# Matrix.net
KiCad netlist of a schematic drawn in Altium Designer
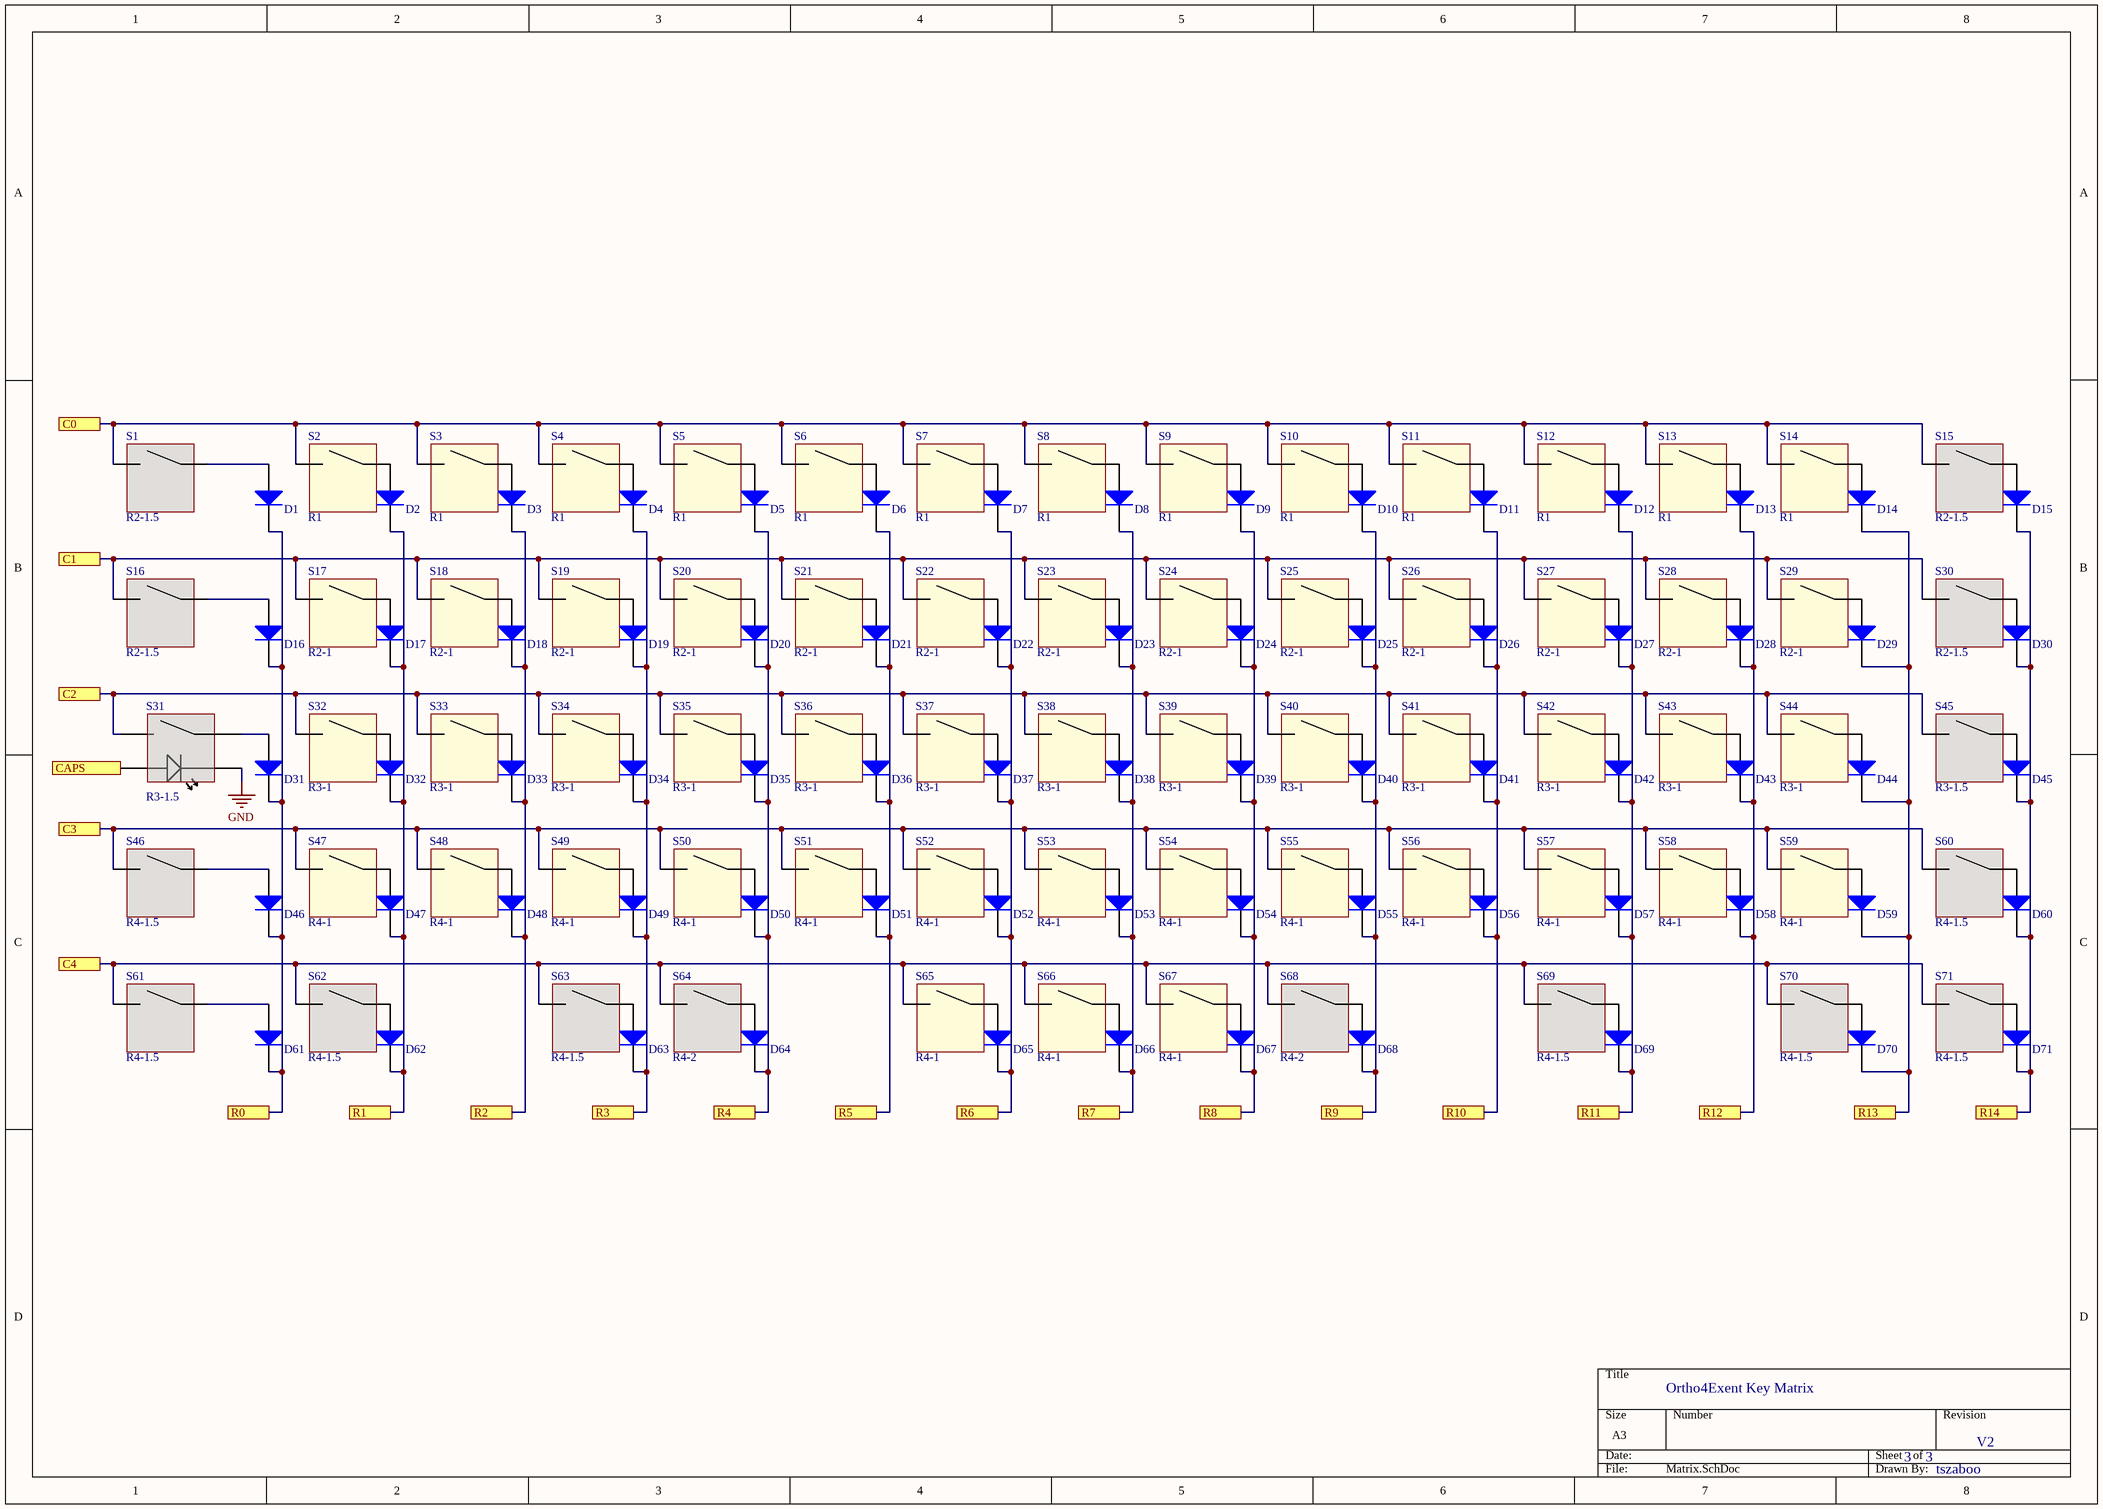
[diagram p0: Matrix.SchDoc]

(export (version "E")
  (design (tool "Eeschema 10.0.6"))
  (components
    (comp (ref "D1")
      (value "1N4148WS")
      (footprint "SOD323FL")
      (description "Default Diode")
      (libsource (lib "Rectifier") (part "Diode"))
    )
    (comp (ref "D2")
      (value "1N4148WS")
      (footprint "SOD323FL")
      (description "Default Diode")
      (libsource (lib "Rectifier") (part "Diode"))
    )
    (comp (ref "D3")
      (value "1N4148WS")
      (footprint "SOD323FL")
      (description "Default Diode")
      (libsource (lib "Rectifier") (part "Diode"))
    )
    (comp (ref "D4")
      (value "1N4148WS")
      (footprint "SOD323FL")
      (description "Default Diode")
      (libsource (lib "Rectifier") (part "Diode"))
    )
    (comp (ref "D5")
      (value "1N4148WS")
      (footprint "SOD323FL")
      (description "Default Diode")
      (libsource (lib "Rectifier") (part "Diode"))
    )
    (comp (ref "D6")
      (value "1N4148WS")
      (footprint "SOD323FL")
      (description "Default Diode")
      (libsource (lib "Rectifier") (part "Diode"))
    )
    (comp (ref "D7")
      (value "1N4148WS")
      (footprint "SOD323FL")
      (description "Default Diode")
      (libsource (lib "Rectifier") (part "Diode"))
    )
    (comp (ref "D8")
      (value "1N4148WS")
      (footprint "SOD323FL")
      (description "Default Diode")
      (libsource (lib "Rectifier") (part "Diode"))
    )
    (comp (ref "D9")
      (value "1N4148WS")
      (footprint "SOD323FL")
      (description "Default Diode")
      (libsource (lib "Rectifier") (part "Diode"))
    )
    (comp (ref "D10")
      (value "1N4148WS")
      (footprint "SOD323FL")
      (description "Default Diode")
      (libsource (lib "Rectifier") (part "Diode"))
    )
    (comp (ref "D11")
      (value "1N4148WS")
      (footprint "SOD323FL")
      (description "Default Diode")
      (libsource (lib "Rectifier") (part "Diode"))
    )
    (comp (ref "D12")
      (value "1N4148WS")
      (footprint "SOD323FL")
      (description "Default Diode")
      (libsource (lib "Rectifier") (part "Diode"))
    )
    (comp (ref "D13")
      (value "1N4148WS")
      (footprint "SOD323FL")
      (description "Default Diode")
      (libsource (lib "Rectifier") (part "Diode"))
    )
    (comp (ref "D14")
      (value "1N4148WS")
      (footprint "SOD323FL")
      (description "Default Diode")
      (libsource (lib "Rectifier") (part "Diode"))
    )
    (comp (ref "D15")
      (value "1N4148WS")
      (footprint "SOD323FL")
      (description "Default Diode")
      (libsource (lib "Rectifier") (part "Diode"))
    )
    (comp (ref "D16")
      (value "1N4148WS")
      (footprint "SOD323FL")
      (description "Default Diode")
      (libsource (lib "Rectifier") (part "Diode"))
    )
    (comp (ref "D17")
      (value "1N4148WS")
      (footprint "SOD323FL")
      (description "Default Diode")
      (libsource (lib "Rectifier") (part "Diode"))
    )
    (comp (ref "D18")
      (value "1N4148WS")
      (footprint "SOD323FL")
      (description "Default Diode")
      (libsource (lib "Rectifier") (part "Diode"))
    )
    (comp (ref "D19")
      (value "1N4148WS")
      (footprint "SOD323FL")
      (description "Default Diode")
      (libsource (lib "Rectifier") (part "Diode"))
    )
    (comp (ref "D20")
      (value "1N4148WS")
      (footprint "SOD323FL")
      (description "Default Diode")
      (libsource (lib "Rectifier") (part "Diode"))
    )
    (comp (ref "D21")
      (value "1N4148WS")
      (footprint "SOD323FL")
      (description "Default Diode")
      (libsource (lib "Rectifier") (part "Diode"))
    )
    (comp (ref "D22")
      (value "1N4148WS")
      (footprint "SOD323FL")
      (description "Default Diode")
      (libsource (lib "Rectifier") (part "Diode"))
    )
    (comp (ref "D23")
      (value "1N4148WS")
      (footprint "SOD323FL")
      (description "Default Diode")
      (libsource (lib "Rectifier") (part "Diode"))
    )
    (comp (ref "D24")
      (value "1N4148WS")
      (footprint "SOD323FL")
      (description "Default Diode")
      (libsource (lib "Rectifier") (part "Diode"))
    )
    (comp (ref "D25")
      (value "1N4148WS")
      (footprint "SOD323FL")
      (description "Default Diode")
      (libsource (lib "Rectifier") (part "Diode"))
    )
    (comp (ref "D26")
      (value "1N4148WS")
      (footprint "SOD323FL")
      (description "Default Diode")
      (libsource (lib "Rectifier") (part "Diode"))
    )
    (comp (ref "D27")
      (value "1N4148WS")
      (footprint "SOD323FL")
      (description "Default Diode")
      (libsource (lib "Rectifier") (part "Diode"))
    )
    (comp (ref "D28")
      (value "1N4148WS")
      (footprint "SOD323FL")
      (description "Default Diode")
      (libsource (lib "Rectifier") (part "Diode"))
    )
    (comp (ref "D29")
      (value "1N4148WS")
      (footprint "SOD323FL")
      (description "Default Diode")
      (libsource (lib "Rectifier") (part "Diode"))
    )
    (comp (ref "D30")
      (value "1N4148WS")
      (footprint "SOD323FL")
      (description "Default Diode")
      (libsource (lib "Rectifier") (part "Diode"))
    )
    (comp (ref "D31")
      (value "1N4148WS")
      (footprint "SOD323FL")
      (description "Default Diode")
      (libsource (lib "Rectifier") (part "Diode"))
    )
    (comp (ref "D32")
      (value "1N4148WS")
      (footprint "SOD323FL")
      (description "Default Diode")
      (libsource (lib "Rectifier") (part "Diode"))
    )
    (comp (ref "D33")
      (value "1N4148WS")
      (footprint "SOD323FL")
      (description "Default Diode")
      (libsource (lib "Rectifier") (part "Diode"))
    )
    (comp (ref "D34")
      (value "1N4148WS")
      (footprint "SOD323FL")
      (description "Default Diode")
      (libsource (lib "Rectifier") (part "Diode"))
    )
    (comp (ref "D35")
      (value "1N4148WS")
      (footprint "SOD323FL")
      (description "Default Diode")
      (libsource (lib "Rectifier") (part "Diode"))
    )
    (comp (ref "D36")
      (value "1N4148WS")
      (footprint "SOD323FL")
      (description "Default Diode")
      (libsource (lib "Rectifier") (part "Diode"))
    )
    (comp (ref "D37")
      (value "1N4148WS")
      (footprint "SOD323FL")
      (description "Default Diode")
      (libsource (lib "Rectifier") (part "Diode"))
    )
    (comp (ref "D38")
      (value "1N4148WS")
      (footprint "SOD323FL")
      (description "Default Diode")
      (libsource (lib "Rectifier") (part "Diode"))
    )
    (comp (ref "D39")
      (value "1N4148WS")
      (footprint "SOD323FL")
      (description "Default Diode")
      (libsource (lib "Rectifier") (part "Diode"))
    )
    (comp (ref "D40")
      (value "1N4148WS")
      (footprint "SOD323FL")
      (description "Default Diode")
      (libsource (lib "Rectifier") (part "Diode"))
    )
    (comp (ref "D41")
      (value "1N4148WS")
      (footprint "SOD323FL")
      (description "Default Diode")
      (libsource (lib "Rectifier") (part "Diode"))
    )
    (comp (ref "D42")
      (value "1N4148WS")
      (footprint "SOD323FL")
      (description "Default Diode")
      (libsource (lib "Rectifier") (part "Diode"))
    )
    (comp (ref "D43")
      (value "1N4148WS")
      (footprint "SOD323FL")
      (description "Default Diode")
      (libsource (lib "Rectifier") (part "Diode"))
    )
    (comp (ref "D44")
      (value "1N4148WS")
      (footprint "SOD323FL")
      (description "Default Diode")
      (libsource (lib "Rectifier") (part "Diode"))
    )
    (comp (ref "D45")
      (value "1N4148WS")
      (footprint "SOD323FL")
      (description "Default Diode")
      (libsource (lib "Rectifier") (part "Diode"))
    )
    (comp (ref "D46")
      (value "1N4148WS")
      (footprint "SOD323FL")
      (description "Default Diode")
      (libsource (lib "Rectifier") (part "Diode"))
    )
    (comp (ref "D47")
      (value "1N4148WS")
      (footprint "SOD323FL")
      (description "Default Diode")
      (libsource (lib "Rectifier") (part "Diode"))
    )
    (comp (ref "D48")
      (value "1N4148WS")
      (footprint "SOD323FL")
      (description "Default Diode")
      (libsource (lib "Rectifier") (part "Diode"))
    )
    (comp (ref "D49")
      (value "1N4148WS")
      (footprint "SOD323FL")
      (description "Default Diode")
      (libsource (lib "Rectifier") (part "Diode"))
    )
    (comp (ref "D50")
      (value "1N4148WS")
      (footprint "SOD323FL")
      (description "Default Diode")
      (libsource (lib "Rectifier") (part "Diode"))
    )
    (comp (ref "D51")
      (value "1N4148WS")
      (footprint "SOD323FL")
      (description "Default Diode")
      (libsource (lib "Rectifier") (part "Diode"))
    )
    (comp (ref "D52")
      (value "1N4148WS")
      (footprint "SOD323FL")
      (description "Default Diode")
      (libsource (lib "Rectifier") (part "Diode"))
    )
    (comp (ref "D53")
      (value "1N4148WS")
      (footprint "SOD323FL")
      (description "Default Diode")
      (libsource (lib "Rectifier") (part "Diode"))
    )
    (comp (ref "D54")
      (value "1N4148WS")
      (footprint "SOD323FL")
      (description "Default Diode")
      (libsource (lib "Rectifier") (part "Diode"))
    )
    (comp (ref "D55")
      (value "1N4148WS")
      (footprint "SOD323FL")
      (description "Default Diode")
      (libsource (lib "Rectifier") (part "Diode"))
    )
    (comp (ref "D56")
      (value "1N4148WS")
      (footprint "SOD323FL")
      (description "Default Diode")
      (libsource (lib "Rectifier") (part "Diode"))
    )
    (comp (ref "D57")
      (value "1N4148WS")
      (footprint "SOD323FL")
      (description "Default Diode")
      (libsource (lib "Rectifier") (part "Diode"))
    )
    (comp (ref "D58")
      (value "1N4148WS")
      (footprint "SOD323FL")
      (description "Default Diode")
      (libsource (lib "Rectifier") (part "Diode"))
    )
    (comp (ref "D59")
      (value "1N4148WS")
      (footprint "SOD323FL")
      (description "Default Diode")
      (libsource (lib "Rectifier") (part "Diode"))
    )
    (comp (ref "D60")
      (value "1N4148WS")
      (footprint "SOD323FL")
      (description "Default Diode")
      (libsource (lib "Rectifier") (part "Diode"))
    )
    (comp (ref "D61")
      (value "1N4148WS")
      (footprint "SOD323FL")
      (description "Default Diode")
      (libsource (lib "Rectifier") (part "Diode"))
    )
    (comp (ref "D62")
      (value "1N4148WS")
      (footprint "SOD323FL")
      (description "Default Diode")
      (libsource (lib "Rectifier") (part "Diode"))
    )
    (comp (ref "D63")
      (value "1N4148WS")
      (footprint "SOD323FL")
      (description "Default Diode")
      (libsource (lib "Rectifier") (part "Diode"))
    )
    (comp (ref "D64")
      (value "1N4148WS")
      (footprint "SOD323FL")
      (description "Default Diode")
      (libsource (lib "Rectifier") (part "Diode"))
    )
    (comp (ref "D65")
      (value "1N4148WS")
      (footprint "SOD323FL")
      (description "Default Diode")
      (libsource (lib "Rectifier") (part "Diode"))
    )
    (comp (ref "D66")
      (value "1N4148WS")
      (footprint "SOD323FL")
      (description "Default Diode")
      (libsource (lib "Rectifier") (part "Diode"))
    )
    (comp (ref "D67")
      (value "1N4148WS")
      (footprint "SOD323FL")
      (description "Default Diode")
      (libsource (lib "Rectifier") (part "Diode"))
    )
    (comp (ref "D68")
      (value "1N4148WS")
      (footprint "SOD323FL")
      (description "Default Diode")
      (libsource (lib "Rectifier") (part "Diode"))
    )
    (comp (ref "D69")
      (value "1N4148WS")
      (footprint "SOD323FL")
      (description "Default Diode")
      (libsource (lib "Rectifier") (part "Diode"))
    )
    (comp (ref "D70")
      (value "1N4148WS")
      (footprint "SOD323FL")
      (description "Default Diode")
      (libsource (lib "Rectifier") (part "Diode"))
    )
    (comp (ref "D71")
      (value "1N4148WS")
      (footprint "SOD323FL")
      (description "Default Diode")
      (libsource (lib "Rectifier") (part "Diode"))
    )
    (comp (ref "S1")
      (value "R2-1.5")
      (footprint "MX:R2-1.5 NOLED")
      (libsource (lib "MX-NOLED") (part "R2-1.5"))
    )
    (comp (ref "S2") (value "R1") (footprint "R1 NOLED") (libsource (lib "MX-NOLED") (part "R1")))
    (comp (ref "S3") (value "R1") (footprint "R1 NOLED") (libsource (lib "MX-NOLED") (part "R1")))
    (comp (ref "S4") (value "R1") (footprint "R1 NOLED") (libsource (lib "MX-NOLED") (part "R1")))
    (comp (ref "S5") (value "R1") (footprint "R1 NOLED") (libsource (lib "MX-NOLED") (part "R1")))
    (comp (ref "S6") (value "R1") (footprint "R1 NOLED") (libsource (lib "MX-NOLED") (part "R1")))
    (comp (ref "S7") (value "R1") (footprint "R1 NOLED") (libsource (lib "MX-NOLED") (part "R1")))
    (comp (ref "S8") (value "R1") (footprint "R1-1 NOLED 180") (libsource (lib "MX-NOLED") (part "R1")))
    (comp (ref "S9") (value "R1") (footprint "R1 NOLED") (libsource (lib "MX-NOLED") (part "R1")))
    (comp (ref "S10") (value "R1") (footprint "R1 NOLED") (libsource (lib "MX-NOLED") (part "R1")))
    (comp (ref "S11") (value "R1") (footprint "R1 NOLED") (libsource (lib "MX-NOLED") (part "R1")))
    (comp (ref "S12") (value "R1") (footprint "R1 NOLED") (libsource (lib "MX-NOLED") (part "R1")))
    (comp (ref "S13") (value "R1") (footprint "R1 NOLED") (libsource (lib "MX-NOLED") (part "R1")))
    (comp (ref "S14") (value "R1") (footprint "R1 NOLED") (libsource (lib "MX-NOLED") (part "R1")))
    (comp (ref "S15")
      (value "R2-1.5")
      (footprint "MX:R2-1.5 NOLED")
      (libsource (lib "MX-NOLED") (part "R2-1.5"))
    )
    (comp (ref "S16")
      (value "R2-1.5")
      (footprint "MX:R2-1.5 NOLED")
      (libsource (lib "MX-NOLED") (part "R2-1.5"))
    )
    (comp (ref "S17") (value "R2-1") (footprint "R2-1 NOLED") (libsource (lib "MX-NOLED") (part "R2-1")))
    (comp (ref "S18") (value "R2-1") (footprint "R2-1 NOLED") (libsource (lib "MX-NOLED") (part "R2-1")))
    (comp (ref "S19") (value "R2-1") (footprint "R2-1 NOLED") (libsource (lib "MX-NOLED") (part "R2-1")))
    (comp (ref "S20") (value "R2-1") (footprint "R2-1 NOLED") (libsource (lib "MX-NOLED") (part "R2-1")))
    (comp (ref "S21") (value "R2-1") (footprint "R2-1 NOLED") (libsource (lib "MX-NOLED") (part "R2-1")))
    (comp (ref "S22") (value "R2-1") (footprint "R2-1 NOLED") (libsource (lib "MX-NOLED") (part "R2-1")))
    (comp (ref "S23") (value "R2-1") (footprint "R2-1 NOLED") (libsource (lib "MX-NOLED") (part "R2-1")))
    (comp (ref "S24") (value "R2-1") (footprint "R2-1 NOLED") (libsource (lib "MX-NOLED") (part "R2-1")))
    (comp (ref "S25") (value "R2-1") (footprint "R2-1 NOLED") (libsource (lib "MX-NOLED") (part "R2-1")))
    (comp (ref "S26") (value "R2-1") (footprint "R2-1 NOLED") (libsource (lib "MX-NOLED") (part "R2-1")))
    (comp (ref "S27") (value "R2-1") (footprint "R2-1 NOLED") (libsource (lib "MX-NOLED") (part "R2-1")))
    (comp (ref "S28") (value "R2-1") (footprint "R2-1 NOLED") (libsource (lib "MX-NOLED") (part "R2-1")))
    (comp (ref "S29") (value "R2-1") (footprint "R2-1 NOLED") (libsource (lib "MX-NOLED") (part "R2-1")))
    (comp (ref "S30")
      (value "R2-1.5")
      (footprint "MX:R2-1.5 NOLED")
      (libsource (lib "MX-NOLED") (part "R2-1.5"))
    )
    (comp (ref "S31") (value "R3-1.5") (footprint "R3-1.5") (libsource (lib "MX") (part "R3-1.5")))
    (comp (ref "S32") (value "R3-1") (footprint "R3-1 NOLED") (libsource (lib "MX-NOLED") (part "R3-1")))
    (comp (ref "S33") (value "R3-1") (footprint "R3-1 NOLED") (libsource (lib "MX-NOLED") (part "R3-1")))
    (comp (ref "S34") (value "R3-1") (footprint "R3-1 NOLED") (libsource (lib "MX-NOLED") (part "R3-1")))
    (comp (ref "S35") (value "R3-1") (footprint "R3-1 NOLED") (libsource (lib "MX-NOLED") (part "R3-1")))
    (comp (ref "S36") (value "R3-1") (footprint "R3-1 NOLED") (libsource (lib "MX-NOLED") (part "R3-1")))
    (comp (ref "S37") (value "R3-1") (footprint "R3-1 NOLED") (libsource (lib "MX-NOLED") (part "R3-1")))
    (comp (ref "S38") (value "R3-1") (footprint "R3-1 NOLED") (libsource (lib "MX-NOLED") (part "R3-1")))
    (comp (ref "S39") (value "R3-1") (footprint "R3-1 NOLED") (libsource (lib "MX-NOLED") (part "R3-1")))
    (comp (ref "S40") (value "R3-1") (footprint "R3-1 NOLED") (libsource (lib "MX-NOLED") (part "R3-1")))
    (comp (ref "S41") (value "R3-1") (footprint "R3-1 NOLED") (libsource (lib "MX-NOLED") (part "R3-1")))
    (comp (ref "S42") (value "R3-1") (footprint "R3-1 NOLED") (libsource (lib "MX-NOLED") (part "R3-1")))
    (comp (ref "S43") (value "R3-1") (footprint "R3-1 NOLED") (libsource (lib "MX-NOLED") (part "R3-1")))
    (comp (ref "S44") (value "R3-1") (footprint "R3-1 NOLED") (libsource (lib "MX-NOLED") (part "R3-1")))
    (comp (ref "S45")
      (value "R3-1.5")
      (footprint "R3-1.5 NOLED")
      (libsource (lib "MX-NOLED") (part "R3-1.5"))
    )
    (comp (ref "S46")
      (value "R4-1.5")
      (footprint "R4-1.5 NOLED")
      (libsource (lib "MX-NOLED") (part "R4-1.5"))
    )
    (comp (ref "S47") (value "R4-1") (footprint "R4-1 NOLED") (libsource (lib "MX-NOLED") (part "R4-1")))
    (comp (ref "S48") (value "R4-1") (footprint "R4-1 NOLED") (libsource (lib "MX-NOLED") (part "R4-1")))
    (comp (ref "S49") (value "R4-1") (footprint "R4-1 NOLED") (libsource (lib "MX-NOLED") (part "R4-1")))
    (comp (ref "S50") (value "R4-1") (footprint "R4-1 NOLED") (libsource (lib "MX-NOLED") (part "R4-1")))
    (comp (ref "S51") (value "R4-1") (footprint "R4-1 NOLED") (libsource (lib "MX-NOLED") (part "R4-1")))
    (comp (ref "S52") (value "R4-1") (footprint "R4-1 NOLED") (libsource (lib "MX-NOLED") (part "R4-1")))
    (comp (ref "S53") (value "R4-1") (footprint "R4-1 NOLED") (libsource (lib "MX-NOLED") (part "R4-1")))
    (comp (ref "S54") (value "R4-1") (footprint "R4-1 NOLED") (libsource (lib "MX-NOLED") (part "R4-1")))
    (comp (ref "S55") (value "R4-1") (footprint "R4-1 NOLED") (libsource (lib "MX-NOLED") (part "R4-1")))
    (comp (ref "S56") (value "R4-1") (footprint "R4-1 NOLED") (libsource (lib "MX-NOLED") (part "R4-1")))
    (comp (ref "S57") (value "R4-1") (footprint "R4-1 NOLED") (libsource (lib "MX-NOLED") (part "R4-1")))
    (comp (ref "S58") (value "R4-1") (footprint "R4-1 NOLED") (libsource (lib "MX-NOLED") (part "R4-1")))
    (comp (ref "S59") (value "R4-1") (footprint "R4-1 NOLED") (libsource (lib "MX-NOLED") (part "R4-1")))
    (comp (ref "S60")
      (value "R4-1.5")
      (footprint "R4-1.5 NOLED")
      (libsource (lib "MX-NOLED") (part "R4-1.5"))
    )
    (comp (ref "S61")
      (value "R4-1.5")
      (footprint "R4-1.5 NOLED")
      (libsource (lib "MX-NOLED") (part "R4-1.5"))
    )
    (comp (ref "S62")
      (value "R4-1.5")
      (footprint "R4-1.5 NOLED")
      (libsource (lib "MX-NOLED") (part "R4-1.5"))
    )
    (comp (ref "S63")
      (value "R4-1.5")
      (footprint "R4-1.5 NOLED")
      (libsource (lib "MX-NOLED") (part "R4-1.5"))
    )
    (comp (ref "S64") (value "R4-2") (footprint "R4-2 NOLED 180") (libsource (lib "MX-NOLED") (part "R4-2")))
    (comp (ref "S65") (value "R4-1") (footprint "R4-1 NOLED") (libsource (lib "MX-NOLED") (part "R4-1")))
    (comp (ref "S66") (value "R4-1") (footprint "R4-1 NOLED") (libsource (lib "MX-NOLED") (part "R4-1")))
    (comp (ref "S67") (value "R4-1") (footprint "R4-1 NOLED") (libsource (lib "MX-NOLED") (part "R4-1")))
    (comp (ref "S68") (value "R4-2") (footprint "R4-2 NOLED 180") (libsource (lib "MX-NOLED") (part "R4-2")))
    (comp (ref "S69")
      (value "R4-1.5")
      (footprint "R4-1.5 NOLED")
      (libsource (lib "MX-NOLED") (part "R4-1.5"))
    )
    (comp (ref "S70")
      (value "R4-1.5")
      (footprint "R4-1.5 NOLED")
      (libsource (lib "MX-NOLED") (part "R4-1.5"))
    )
    (comp (ref "S71")
      (value "R4-1.5")
      (footprint "R4-1.5 NOLED")
      (libsource (lib "MX-NOLED") (part "R4-1.5"))
    )
  )
  (nets
    (net (code "1") (name "/C0") (class "Default")
      (node (ref "S1") (pin "1") (pinfunction "1_1") (pintype "passive"))
      (node (ref "S10") (pin "1") (pinfunction "1_1") (pintype "passive"))
      (node (ref "S11") (pin "1") (pinfunction "1_1") (pintype "passive"))
      (node (ref "S12") (pin "1") (pinfunction "1_1") (pintype "passive"))
      (node (ref "S13") (pin "1") (pinfunction "1_1") (pintype "passive"))
      (node (ref "S14") (pin "1") (pinfunction "1_1") (pintype "passive"))
      (node (ref "S15") (pin "1") (pinfunction "1_1") (pintype "passive"))
      (node (ref "S2") (pin "1") (pinfunction "1_1") (pintype "passive"))
      (node (ref "S3") (pin "1") (pinfunction "1_1") (pintype "passive"))
      (node (ref "S4") (pin "1") (pinfunction "1_1") (pintype "passive"))
      (node (ref "S5") (pin "1") (pinfunction "1_1") (pintype "passive"))
      (node (ref "S6") (pin "1") (pinfunction "1_1") (pintype "passive"))
      (node (ref "S7") (pin "1") (pinfunction "1_1") (pintype "passive"))
      (node (ref "S8") (pin "1") (pinfunction "1_1") (pintype "passive"))
      (node (ref "S9") (pin "1") (pinfunction "1_1") (pintype "passive"))
    )
    (net (code "2") (name "/C1") (class "Default")
      (node (ref "S16") (pin "1") (pinfunction "1_1") (pintype "passive"))
      (node (ref "S17") (pin "1") (pinfunction "1_1") (pintype "passive"))
      (node (ref "S18") (pin "1") (pinfunction "1_1") (pintype "passive"))
      (node (ref "S19") (pin "1") (pinfunction "1_1") (pintype "passive"))
      (node (ref "S20") (pin "1") (pinfunction "1_1") (pintype "passive"))
      (node (ref "S21") (pin "1") (pinfunction "1_1") (pintype "passive"))
      (node (ref "S22") (pin "1") (pinfunction "1_1") (pintype "passive"))
      (node (ref "S23") (pin "1") (pinfunction "1_1") (pintype "passive"))
      (node (ref "S24") (pin "1") (pinfunction "1_1") (pintype "passive"))
      (node (ref "S25") (pin "1") (pinfunction "1_1") (pintype "passive"))
      (node (ref "S26") (pin "1") (pinfunction "1_1") (pintype "passive"))
      (node (ref "S27") (pin "1") (pinfunction "1_1") (pintype "passive"))
      (node (ref "S28") (pin "1") (pinfunction "1_1") (pintype "passive"))
      (node (ref "S29") (pin "1") (pinfunction "1_1") (pintype "passive"))
      (node (ref "S30") (pin "1") (pinfunction "1_1") (pintype "passive"))
    )
    (net (code "3") (name "/C2") (class "Default")
      (node (ref "S31") (pin "1") (pinfunction "1_1") (pintype "passive"))
      (node (ref "S32") (pin "1") (pinfunction "1_1") (pintype "passive"))
      (node (ref "S33") (pin "1") (pinfunction "1_1") (pintype "passive"))
      (node (ref "S34") (pin "1") (pinfunction "1_1") (pintype "passive"))
      (node (ref "S35") (pin "1") (pinfunction "1_1") (pintype "passive"))
      (node (ref "S36") (pin "1") (pinfunction "1_1") (pintype "passive"))
      (node (ref "S37") (pin "1") (pinfunction "1_1") (pintype "passive"))
      (node (ref "S38") (pin "1") (pinfunction "1_1") (pintype "passive"))
      (node (ref "S39") (pin "1") (pinfunction "1_1") (pintype "passive"))
      (node (ref "S40") (pin "1") (pinfunction "1_1") (pintype "passive"))
      (node (ref "S41") (pin "1") (pinfunction "1_1") (pintype "passive"))
      (node (ref "S42") (pin "1") (pinfunction "1_1") (pintype "passive"))
      (node (ref "S43") (pin "1") (pinfunction "1_1") (pintype "passive"))
      (node (ref "S44") (pin "1") (pinfunction "1_1") (pintype "passive"))
      (node (ref "S45") (pin "1") (pinfunction "1_1") (pintype "passive"))
    )
    (net (code "4") (name "/C3") (class "Default")
      (node (ref "S46") (pin "1") (pinfunction "1_1") (pintype "passive"))
      (node (ref "S47") (pin "1") (pinfunction "1_1") (pintype "passive"))
      (node (ref "S48") (pin "1") (pinfunction "1_1") (pintype "passive"))
      (node (ref "S49") (pin "1") (pinfunction "1_1") (pintype "passive"))
      (node (ref "S50") (pin "1") (pinfunction "1_1") (pintype "passive"))
      (node (ref "S51") (pin "1") (pinfunction "1_1") (pintype "passive"))
      (node (ref "S52") (pin "1") (pinfunction "1_1") (pintype "passive"))
      (node (ref "S53") (pin "1") (pinfunction "1_1") (pintype "passive"))
      (node (ref "S54") (pin "1") (pinfunction "1_1") (pintype "passive"))
      (node (ref "S55") (pin "1") (pinfunction "1_1") (pintype "passive"))
      (node (ref "S56") (pin "1") (pinfunction "1_1") (pintype "passive"))
      (node (ref "S57") (pin "1") (pinfunction "1_1") (pintype "passive"))
      (node (ref "S58") (pin "1") (pinfunction "1_1") (pintype "passive"))
      (node (ref "S59") (pin "1") (pinfunction "1_1") (pintype "passive"))
      (node (ref "S60") (pin "1") (pinfunction "1_1") (pintype "passive"))
    )
    (net (code "5") (name "/C4") (class "Default")
      (node (ref "S61") (pin "1") (pinfunction "1_1") (pintype "passive"))
      (node (ref "S62") (pin "1") (pinfunction "1_1") (pintype "passive"))
      (node (ref "S63") (pin "1") (pinfunction "1_1") (pintype "passive"))
      (node (ref "S64") (pin "1") (pinfunction "1_1") (pintype "passive"))
      (node (ref "S65") (pin "1") (pinfunction "1_1") (pintype "passive"))
      (node (ref "S66") (pin "1") (pinfunction "1_1") (pintype "passive"))
      (node (ref "S67") (pin "1") (pinfunction "1_1") (pintype "passive"))
      (node (ref "S68") (pin "1") (pinfunction "1_1") (pintype "passive"))
      (node (ref "S69") (pin "1") (pinfunction "1_1") (pintype "passive"))
      (node (ref "S70") (pin "1") (pinfunction "1_1") (pintype "passive"))
      (node (ref "S71") (pin "1") (pinfunction "1_1") (pintype "passive"))
    )
    (net (code "6") (name "/CAPS") (class "Default")
      (node (ref "S31") (pin "4") (pinfunction "4_4") (pintype "passive"))
    )
    (net (code "7") (name "/R0") (class "Default")
      (node (ref "D1") (pin "2") (pinfunction "K_2") (pintype "passive"))
      (node (ref "D16") (pin "2") (pinfunction "K_2") (pintype "passive"))
      (node (ref "D31") (pin "2") (pinfunction "K_2") (pintype "passive"))
      (node (ref "D46") (pin "2") (pinfunction "K_2") (pintype "passive"))
      (node (ref "D61") (pin "2") (pinfunction "K_2") (pintype "passive"))
    )
    (net (code "8") (name "/R1") (class "Default")
      (node (ref "D17") (pin "2") (pinfunction "K_2") (pintype "passive"))
      (node (ref "D2") (pin "2") (pinfunction "K_2") (pintype "passive"))
      (node (ref "D32") (pin "2") (pinfunction "K_2") (pintype "passive"))
      (node (ref "D47") (pin "2") (pinfunction "K_2") (pintype "passive"))
      (node (ref "D62") (pin "2") (pinfunction "K_2") (pintype "passive"))
    )
    (net (code "9") (name "/R2") (class "Default")
      (node (ref "D18") (pin "2") (pinfunction "K_2") (pintype "passive"))
      (node (ref "D3") (pin "2") (pinfunction "K_2") (pintype "passive"))
      (node (ref "D33") (pin "2") (pinfunction "K_2") (pintype "passive"))
      (node (ref "D48") (pin "2") (pinfunction "K_2") (pintype "passive"))
    )
    (net (code "10") (name "/R3") (class "Default")
      (node (ref "D19") (pin "2") (pinfunction "K_2") (pintype "passive"))
      (node (ref "D34") (pin "2") (pinfunction "K_2") (pintype "passive"))
      (node (ref "D4") (pin "2") (pinfunction "K_2") (pintype "passive"))
      (node (ref "D49") (pin "2") (pinfunction "K_2") (pintype "passive"))
      (node (ref "D63") (pin "2") (pinfunction "K_2") (pintype "passive"))
    )
    (net (code "11") (name "/R4") (class "Default")
      (node (ref "D20") (pin "2") (pinfunction "K_2") (pintype "passive"))
      (node (ref "D35") (pin "2") (pinfunction "K_2") (pintype "passive"))
      (node (ref "D5") (pin "2") (pinfunction "K_2") (pintype "passive"))
      (node (ref "D50") (pin "2") (pinfunction "K_2") (pintype "passive"))
      (node (ref "D64") (pin "2") (pinfunction "K_2") (pintype "passive"))
    )
    (net (code "12") (name "/R5") (class "Default")
      (node (ref "D21") (pin "2") (pinfunction "K_2") (pintype "passive"))
      (node (ref "D36") (pin "2") (pinfunction "K_2") (pintype "passive"))
      (node (ref "D51") (pin "2") (pinfunction "K_2") (pintype "passive"))
      (node (ref "D6") (pin "2") (pinfunction "K_2") (pintype "passive"))
    )
    (net (code "13") (name "/R6") (class "Default")
      (node (ref "D22") (pin "2") (pinfunction "K_2") (pintype "passive"))
      (node (ref "D37") (pin "2") (pinfunction "K_2") (pintype "passive"))
      (node (ref "D52") (pin "2") (pinfunction "K_2") (pintype "passive"))
      (node (ref "D65") (pin "2") (pinfunction "K_2") (pintype "passive"))
      (node (ref "D7") (pin "2") (pinfunction "K_2") (pintype "passive"))
    )
    (net (code "14") (name "/R7") (class "Default")
      (node (ref "D23") (pin "2") (pinfunction "K_2") (pintype "passive"))
      (node (ref "D38") (pin "2") (pinfunction "K_2") (pintype "passive"))
      (node (ref "D53") (pin "2") (pinfunction "K_2") (pintype "passive"))
      (node (ref "D66") (pin "2") (pinfunction "K_2") (pintype "passive"))
      (node (ref "D8") (pin "2") (pinfunction "K_2") (pintype "passive"))
    )
    (net (code "15") (name "/R8") (class "Default")
      (node (ref "D24") (pin "2") (pinfunction "K_2") (pintype "passive"))
      (node (ref "D39") (pin "2") (pinfunction "K_2") (pintype "passive"))
      (node (ref "D54") (pin "2") (pinfunction "K_2") (pintype "passive"))
      (node (ref "D67") (pin "2") (pinfunction "K_2") (pintype "passive"))
      (node (ref "D9") (pin "2") (pinfunction "K_2") (pintype "passive"))
    )
    (net (code "16") (name "/R9") (class "Default")
      (node (ref "D10") (pin "2") (pinfunction "K_2") (pintype "passive"))
      (node (ref "D25") (pin "2") (pinfunction "K_2") (pintype "passive"))
      (node (ref "D40") (pin "2") (pinfunction "K_2") (pintype "passive"))
      (node (ref "D55") (pin "2") (pinfunction "K_2") (pintype "passive"))
      (node (ref "D68") (pin "2") (pinfunction "K_2") (pintype "passive"))
    )
    (net (code "17") (name "/R10") (class "Default")
      (node (ref "D11") (pin "2") (pinfunction "K_2") (pintype "passive"))
      (node (ref "D26") (pin "2") (pinfunction "K_2") (pintype "passive"))
      (node (ref "D41") (pin "2") (pinfunction "K_2") (pintype "passive"))
      (node (ref "D56") (pin "2") (pinfunction "K_2") (pintype "passive"))
    )
    (net (code "18") (name "/R11") (class "Default")
      (node (ref "D12") (pin "2") (pinfunction "K_2") (pintype "passive"))
      (node (ref "D27") (pin "2") (pinfunction "K_2") (pintype "passive"))
      (node (ref "D42") (pin "2") (pinfunction "K_2") (pintype "passive"))
      (node (ref "D57") (pin "2") (pinfunction "K_2") (pintype "passive"))
      (node (ref "D69") (pin "2") (pinfunction "K_2") (pintype "passive"))
    )
    (net (code "19") (name "/R12") (class "Default")
      (node (ref "D13") (pin "2") (pinfunction "K_2") (pintype "passive"))
      (node (ref "D28") (pin "2") (pinfunction "K_2") (pintype "passive"))
      (node (ref "D43") (pin "2") (pinfunction "K_2") (pintype "passive"))
      (node (ref "D58") (pin "2") (pinfunction "K_2") (pintype "passive"))
    )
    (net (code "20") (name "/R13") (class "Default")
      (node (ref "D14") (pin "2") (pinfunction "K_2") (pintype "passive"))
      (node (ref "D29") (pin "2") (pinfunction "K_2") (pintype "passive"))
      (node (ref "D44") (pin "2") (pinfunction "K_2") (pintype "passive"))
      (node (ref "D59") (pin "2") (pinfunction "K_2") (pintype "passive"))
      (node (ref "D70") (pin "2") (pinfunction "K_2") (pintype "passive"))
    )
    (net (code "21") (name "/R14") (class "Default")
      (node (ref "D15") (pin "2") (pinfunction "K_2") (pintype "passive"))
      (node (ref "D30") (pin "2") (pinfunction "K_2") (pintype "passive"))
      (node (ref "D45") (pin "2") (pinfunction "K_2") (pintype "passive"))
      (node (ref "D60") (pin "2") (pinfunction "K_2") (pintype "passive"))
      (node (ref "D71") (pin "2") (pinfunction "K_2") (pintype "passive"))
    )
    (net (code "22") (name "GND") (class "Default")
      (node (ref "S31") (pin "3") (pinfunction "3_3") (pintype "passive"))
    )
    (net (code "23") (name "Net-(D1-A)") (class "Default")
      (node (ref "D1") (pin "1") (pinfunction "A_1") (pintype "passive"))
      (node (ref "S1") (pin "2") (pinfunction "2_2") (pintype "passive"))
    )
    (net (code "24") (name "Net-(D2-A)") (class "Default")
      (node (ref "D2") (pin "1") (pinfunction "A_1") (pintype "passive"))
      (node (ref "S2") (pin "2") (pinfunction "2_2") (pintype "passive"))
    )
    (net (code "25") (name "Net-(D3-A)") (class "Default")
      (node (ref "D3") (pin "1") (pinfunction "A_1") (pintype "passive"))
      (node (ref "S3") (pin "2") (pinfunction "2_2") (pintype "passive"))
    )
    (net (code "26") (name "Net-(D4-A)") (class "Default")
      (node (ref "D4") (pin "1") (pinfunction "A_1") (pintype "passive"))
      (node (ref "S4") (pin "2") (pinfunction "2_2") (pintype "passive"))
    )
    (net (code "27") (name "Net-(D5-A)") (class "Default")
      (node (ref "D5") (pin "1") (pinfunction "A_1") (pintype "passive"))
      (node (ref "S5") (pin "2") (pinfunction "2_2") (pintype "passive"))
    )
    (net (code "28") (name "Net-(D6-A)") (class "Default")
      (node (ref "D6") (pin "1") (pinfunction "A_1") (pintype "passive"))
      (node (ref "S6") (pin "2") (pinfunction "2_2") (pintype "passive"))
    )
    (net (code "29") (name "Net-(D7-A)") (class "Default")
      (node (ref "D7") (pin "1") (pinfunction "A_1") (pintype "passive"))
      (node (ref "S7") (pin "2") (pinfunction "2_2") (pintype "passive"))
    )
    (net (code "30") (name "Net-(D8-A)") (class "Default")
      (node (ref "D8") (pin "1") (pinfunction "A_1") (pintype "passive"))
      (node (ref "S8") (pin "2") (pinfunction "2_2") (pintype "passive"))
    )
    (net (code "31") (name "Net-(D9-A)") (class "Default")
      (node (ref "D9") (pin "1") (pinfunction "A_1") (pintype "passive"))
      (node (ref "S9") (pin "2") (pinfunction "2_2") (pintype "passive"))
    )
    (net (code "32") (name "Net-(D10-A)") (class "Default")
      (node (ref "D10") (pin "1") (pinfunction "A_1") (pintype "passive"))
      (node (ref "S10") (pin "2") (pinfunction "2_2") (pintype "passive"))
    )
    (net (code "33") (name "Net-(D11-A)") (class "Default")
      (node (ref "D11") (pin "1") (pinfunction "A_1") (pintype "passive"))
      (node (ref "S11") (pin "2") (pinfunction "2_2") (pintype "passive"))
    )
    (net (code "34") (name "Net-(D12-A)") (class "Default")
      (node (ref "D12") (pin "1") (pinfunction "A_1") (pintype "passive"))
      (node (ref "S12") (pin "2") (pinfunction "2_2") (pintype "passive"))
    )
    (net (code "35") (name "Net-(D13-A)") (class "Default")
      (node (ref "D13") (pin "1") (pinfunction "A_1") (pintype "passive"))
      (node (ref "S13") (pin "2") (pinfunction "2_2") (pintype "passive"))
    )
    (net (code "36") (name "Net-(D14-A)") (class "Default")
      (node (ref "D14") (pin "1") (pinfunction "A_1") (pintype "passive"))
      (node (ref "S14") (pin "2") (pinfunction "2_2") (pintype "passive"))
    )
    (net (code "37") (name "Net-(D15-A)") (class "Default")
      (node (ref "D15") (pin "1") (pinfunction "A_1") (pintype "passive"))
      (node (ref "S15") (pin "2") (pinfunction "2_2") (pintype "passive"))
    )
    (net (code "38") (name "Net-(D16-A)") (class "Default")
      (node (ref "D16") (pin "1") (pinfunction "A_1") (pintype "passive"))
      (node (ref "S16") (pin "2") (pinfunction "2_2") (pintype "passive"))
    )
    (net (code "39") (name "Net-(D17-A)") (class "Default")
      (node (ref "D17") (pin "1") (pinfunction "A_1") (pintype "passive"))
      (node (ref "S17") (pin "2") (pinfunction "2_2") (pintype "passive"))
    )
    (net (code "40") (name "Net-(D18-A)") (class "Default")
      (node (ref "D18") (pin "1") (pinfunction "A_1") (pintype "passive"))
      (node (ref "S18") (pin "2") (pinfunction "2_2") (pintype "passive"))
    )
    (net (code "41") (name "Net-(D19-A)") (class "Default")
      (node (ref "D19") (pin "1") (pinfunction "A_1") (pintype "passive"))
      (node (ref "S19") (pin "2") (pinfunction "2_2") (pintype "passive"))
    )
    (net (code "42") (name "Net-(D20-A)") (class "Default")
      (node (ref "D20") (pin "1") (pinfunction "A_1") (pintype "passive"))
      (node (ref "S20") (pin "2") (pinfunction "2_2") (pintype "passive"))
    )
    (net (code "43") (name "Net-(D21-A)") (class "Default")
      (node (ref "D21") (pin "1") (pinfunction "A_1") (pintype "passive"))
      (node (ref "S21") (pin "2") (pinfunction "2_2") (pintype "passive"))
    )
    (net (code "44") (name "Net-(D22-A)") (class "Default")
      (node (ref "D22") (pin "1") (pinfunction "A_1") (pintype "passive"))
      (node (ref "S22") (pin "2") (pinfunction "2_2") (pintype "passive"))
    )
    (net (code "45") (name "Net-(D23-A)") (class "Default")
      (node (ref "D23") (pin "1") (pinfunction "A_1") (pintype "passive"))
      (node (ref "S23") (pin "2") (pinfunction "2_2") (pintype "passive"))
    )
    (net (code "46") (name "Net-(D24-A)") (class "Default")
      (node (ref "D24") (pin "1") (pinfunction "A_1") (pintype "passive"))
      (node (ref "S24") (pin "2") (pinfunction "2_2") (pintype "passive"))
    )
    (net (code "47") (name "Net-(D25-A)") (class "Default")
      (node (ref "D25") (pin "1") (pinfunction "A_1") (pintype "passive"))
      (node (ref "S25") (pin "2") (pinfunction "2_2") (pintype "passive"))
    )
    (net (code "48") (name "Net-(D26-A)") (class "Default")
      (node (ref "D26") (pin "1") (pinfunction "A_1") (pintype "passive"))
      (node (ref "S26") (pin "2") (pinfunction "2_2") (pintype "passive"))
    )
    (net (code "49") (name "Net-(D27-A)") (class "Default")
      (node (ref "D27") (pin "1") (pinfunction "A_1") (pintype "passive"))
      (node (ref "S27") (pin "2") (pinfunction "2_2") (pintype "passive"))
    )
    (net (code "50") (name "Net-(D28-A)") (class "Default")
      (node (ref "D28") (pin "1") (pinfunction "A_1") (pintype "passive"))
      (node (ref "S28") (pin "2") (pinfunction "2_2") (pintype "passive"))
    )
    (net (code "51") (name "Net-(D29-A)") (class "Default")
      (node (ref "D29") (pin "1") (pinfunction "A_1") (pintype "passive"))
      (node (ref "S29") (pin "2") (pinfunction "2_2") (pintype "passive"))
    )
    (net (code "52") (name "Net-(D30-A)") (class "Default")
      (node (ref "D30") (pin "1") (pinfunction "A_1") (pintype "passive"))
      (node (ref "S30") (pin "2") (pinfunction "2_2") (pintype "passive"))
    )
    (net (code "53") (name "Net-(D31-A)") (class "Default")
      (node (ref "D31") (pin "1") (pinfunction "A_1") (pintype "passive"))
      (node (ref "S31") (pin "2") (pinfunction "2_2") (pintype "passive"))
    )
    (net (code "54") (name "Net-(D32-A)") (class "Default")
      (node (ref "D32") (pin "1") (pinfunction "A_1") (pintype "passive"))
      (node (ref "S32") (pin "2") (pinfunction "2_2") (pintype "passive"))
    )
    (net (code "55") (name "Net-(D33-A)") (class "Default")
      (node (ref "D33") (pin "1") (pinfunction "A_1") (pintype "passive"))
      (node (ref "S33") (pin "2") (pinfunction "2_2") (pintype "passive"))
    )
    (net (code "56") (name "Net-(D34-A)") (class "Default")
      (node (ref "D34") (pin "1") (pinfunction "A_1") (pintype "passive"))
      (node (ref "S34") (pin "2") (pinfunction "2_2") (pintype "passive"))
    )
    (net (code "57") (name "Net-(D35-A)") (class "Default")
      (node (ref "D35") (pin "1") (pinfunction "A_1") (pintype "passive"))
      (node (ref "S35") (pin "2") (pinfunction "2_2") (pintype "passive"))
    )
    (net (code "58") (name "Net-(D36-A)") (class "Default")
      (node (ref "D36") (pin "1") (pinfunction "A_1") (pintype "passive"))
      (node (ref "S36") (pin "2") (pinfunction "2_2") (pintype "passive"))
    )
    (net (code "59") (name "Net-(D37-A)") (class "Default")
      (node (ref "D37") (pin "1") (pinfunction "A_1") (pintype "passive"))
      (node (ref "S37") (pin "2") (pinfunction "2_2") (pintype "passive"))
    )
    (net (code "60") (name "Net-(D38-A)") (class "Default")
      (node (ref "D38") (pin "1") (pinfunction "A_1") (pintype "passive"))
      (node (ref "S38") (pin "2") (pinfunction "2_2") (pintype "passive"))
    )
    (net (code "61") (name "Net-(D39-A)") (class "Default")
      (node (ref "D39") (pin "1") (pinfunction "A_1") (pintype "passive"))
      (node (ref "S39") (pin "2") (pinfunction "2_2") (pintype "passive"))
    )
    (net (code "62") (name "Net-(D40-A)") (class "Default")
      (node (ref "D40") (pin "1") (pinfunction "A_1") (pintype "passive"))
      (node (ref "S40") (pin "2") (pinfunction "2_2") (pintype "passive"))
    )
    (net (code "63") (name "Net-(D41-A)") (class "Default")
      (node (ref "D41") (pin "1") (pinfunction "A_1") (pintype "passive"))
      (node (ref "S41") (pin "2") (pinfunction "2_2") (pintype "passive"))
    )
    (net (code "64") (name "Net-(D42-A)") (class "Default")
      (node (ref "D42") (pin "1") (pinfunction "A_1") (pintype "passive"))
      (node (ref "S42") (pin "2") (pinfunction "2_2") (pintype "passive"))
    )
    (net (code "65") (name "Net-(D43-A)") (class "Default")
      (node (ref "D43") (pin "1") (pinfunction "A_1") (pintype "passive"))
      (node (ref "S43") (pin "2") (pinfunction "2_2") (pintype "passive"))
    )
    (net (code "66") (name "Net-(D44-A)") (class "Default")
      (node (ref "D44") (pin "1") (pinfunction "A_1") (pintype "passive"))
      (node (ref "S44") (pin "2") (pinfunction "2_2") (pintype "passive"))
    )
    (net (code "67") (name "Net-(D45-A)") (class "Default")
      (node (ref "D45") (pin "1") (pinfunction "A_1") (pintype "passive"))
      (node (ref "S45") (pin "2") (pinfunction "2_2") (pintype "passive"))
    )
    (net (code "68") (name "Net-(D46-A)") (class "Default")
      (node (ref "D46") (pin "1") (pinfunction "A_1") (pintype "passive"))
      (node (ref "S46") (pin "2") (pinfunction "2_2") (pintype "passive"))
    )
    (net (code "69") (name "Net-(D47-A)") (class "Default")
      (node (ref "D47") (pin "1") (pinfunction "A_1") (pintype "passive"))
      (node (ref "S47") (pin "2") (pinfunction "2_2") (pintype "passive"))
    )
    (net (code "70") (name "Net-(D48-A)") (class "Default")
      (node (ref "D48") (pin "1") (pinfunction "A_1") (pintype "passive"))
      (node (ref "S48") (pin "2") (pinfunction "2_2") (pintype "passive"))
    )
    (net (code "71") (name "Net-(D49-A)") (class "Default")
      (node (ref "D49") (pin "1") (pinfunction "A_1") (pintype "passive"))
      (node (ref "S49") (pin "2") (pinfunction "2_2") (pintype "passive"))
    )
    (net (code "72") (name "Net-(D50-A)") (class "Default")
      (node (ref "D50") (pin "1") (pinfunction "A_1") (pintype "passive"))
      (node (ref "S50") (pin "2") (pinfunction "2_2") (pintype "passive"))
    )
    (net (code "73") (name "Net-(D51-A)") (class "Default")
      (node (ref "D51") (pin "1") (pinfunction "A_1") (pintype "passive"))
      (node (ref "S51") (pin "2") (pinfunction "2_2") (pintype "passive"))
    )
    (net (code "74") (name "Net-(D52-A)") (class "Default")
      (node (ref "D52") (pin "1") (pinfunction "A_1") (pintype "passive"))
      (node (ref "S52") (pin "2") (pinfunction "2_2") (pintype "passive"))
    )
    (net (code "75") (name "Net-(D53-A)") (class "Default")
      (node (ref "D53") (pin "1") (pinfunction "A_1") (pintype "passive"))
      (node (ref "S53") (pin "2") (pinfunction "2_2") (pintype "passive"))
    )
    (net (code "76") (name "Net-(D54-A)") (class "Default")
      (node (ref "D54") (pin "1") (pinfunction "A_1") (pintype "passive"))
      (node (ref "S54") (pin "2") (pinfunction "2_2") (pintype "passive"))
    )
    (net (code "77") (name "Net-(D55-A)") (class "Default")
      (node (ref "D55") (pin "1") (pinfunction "A_1") (pintype "passive"))
      (node (ref "S55") (pin "2") (pinfunction "2_2") (pintype "passive"))
    )
    (net (code "78") (name "Net-(D56-A)") (class "Default")
      (node (ref "D56") (pin "1") (pinfunction "A_1") (pintype "passive"))
      (node (ref "S56") (pin "2") (pinfunction "2_2") (pintype "passive"))
    )
    (net (code "79") (name "Net-(D57-A)") (class "Default")
      (node (ref "D57") (pin "1") (pinfunction "A_1") (pintype "passive"))
      (node (ref "S57") (pin "2") (pinfunction "2_2") (pintype "passive"))
    )
    (net (code "80") (name "Net-(D58-A)") (class "Default")
      (node (ref "D58") (pin "1") (pinfunction "A_1") (pintype "passive"))
      (node (ref "S58") (pin "2") (pinfunction "2_2") (pintype "passive"))
    )
    (net (code "81") (name "Net-(D59-A)") (class "Default")
      (node (ref "D59") (pin "1") (pinfunction "A_1") (pintype "passive"))
      (node (ref "S59") (pin "2") (pinfunction "2_2") (pintype "passive"))
    )
    (net (code "82") (name "Net-(D60-A)") (class "Default")
      (node (ref "D60") (pin "1") (pinfunction "A_1") (pintype "passive"))
      (node (ref "S60") (pin "2") (pinfunction "2_2") (pintype "passive"))
    )
    (net (code "83") (name "Net-(D61-A)") (class "Default")
      (node (ref "D61") (pin "1") (pinfunction "A_1") (pintype "passive"))
      (node (ref "S61") (pin "2") (pinfunction "2_2") (pintype "passive"))
    )
    (net (code "84") (name "Net-(D62-A)") (class "Default")
      (node (ref "D62") (pin "1") (pinfunction "A_1") (pintype "passive"))
      (node (ref "S62") (pin "2") (pinfunction "2_2") (pintype "passive"))
    )
    (net (code "85") (name "Net-(D63-A)") (class "Default")
      (node (ref "D63") (pin "1") (pinfunction "A_1") (pintype "passive"))
      (node (ref "S63") (pin "2") (pinfunction "2_2") (pintype "passive"))
    )
    (net (code "86") (name "Net-(D64-A)") (class "Default")
      (node (ref "D64") (pin "1") (pinfunction "A_1") (pintype "passive"))
      (node (ref "S64") (pin "2") (pinfunction "2_2") (pintype "passive"))
    )
    (net (code "87") (name "Net-(D65-A)") (class "Default")
      (node (ref "D65") (pin "1") (pinfunction "A_1") (pintype "passive"))
      (node (ref "S65") (pin "2") (pinfunction "2_2") (pintype "passive"))
    )
    (net (code "88") (name "Net-(D66-A)") (class "Default")
      (node (ref "D66") (pin "1") (pinfunction "A_1") (pintype "passive"))
      (node (ref "S66") (pin "2") (pinfunction "2_2") (pintype "passive"))
    )
    (net (code "89") (name "Net-(D67-A)") (class "Default")
      (node (ref "D67") (pin "1") (pinfunction "A_1") (pintype "passive"))
      (node (ref "S67") (pin "2") (pinfunction "2_2") (pintype "passive"))
    )
    (net (code "90") (name "Net-(D68-A)") (class "Default")
      (node (ref "D68") (pin "1") (pinfunction "A_1") (pintype "passive"))
      (node (ref "S68") (pin "2") (pinfunction "2_2") (pintype "passive"))
    )
    (net (code "91") (name "Net-(D69-A)") (class "Default")
      (node (ref "D69") (pin "1") (pinfunction "A_1") (pintype "passive"))
      (node (ref "S69") (pin "2") (pinfunction "2_2") (pintype "passive"))
    )
    (net (code "92") (name "Net-(D70-A)") (class "Default")
      (node (ref "D70") (pin "1") (pinfunction "A_1") (pintype "passive"))
      (node (ref "S70") (pin "2") (pinfunction "2_2") (pintype "passive"))
    )
    (net (code "93") (name "Net-(D71-A)") (class "Default")
      (node (ref "D71") (pin "1") (pinfunction "A_1") (pintype "passive"))
      (node (ref "S71") (pin "2") (pinfunction "2_2") (pintype "passive"))
    )
  )
)
